# Bus.net
KiCad netlist of a schematic drawn in Altium Designer
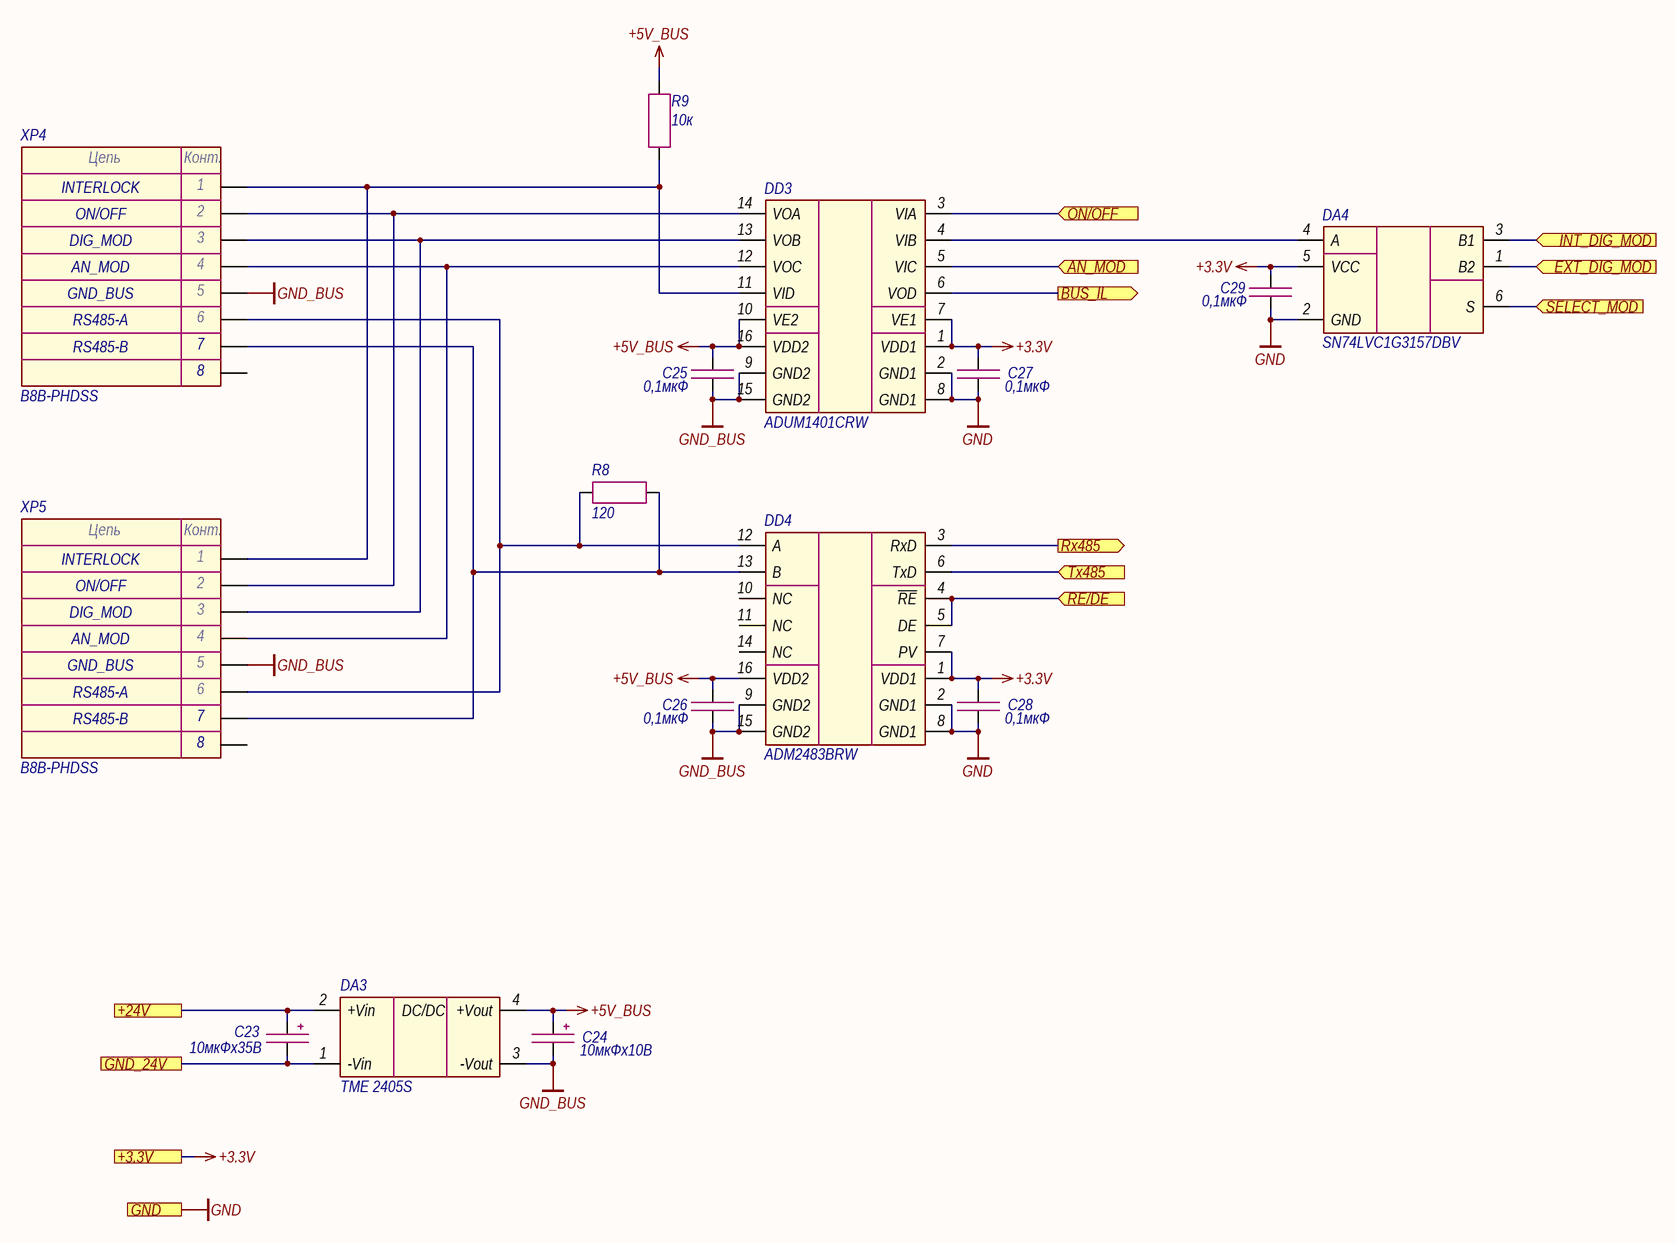
[diagram p0: Bus.SchDoc]

(export (version "E")
  (design (tool "Eeschema 10.0.6"))
  (components
    (comp (ref "C23")
      (value "10мкФх35B")
      (footprint "Pcb_library:CAP_C")
      (libsource (lib "Schem_library") (part "Capacitor_Polar"))
    )
    (comp (ref "C24")
      (value "10мкФх10B")
      (footprint "Pcb_library:CAP_A")
      (libsource (lib "Schem_library") (part "Capacitor_Polar"))
    )
    (comp (ref "C25")
      (value "0,1мкФ")
      (footprint "Pcb_library:CAP_0603")
      (fields (field (name "MANUFACTURER") "Murata"))
      (libsource (lib "Schem_library") (part "Capacitor"))
    )
    (comp (ref "C26")
      (value "0,1мкФ")
      (footprint "Pcb_library:CAP_0603")
      (fields (field (name "MANUFACTURER") "Murata"))
      (libsource (lib "Schem_library") (part "Capacitor"))
    )
    (comp (ref "C27")
      (value "0,1мкФ")
      (footprint "Pcb_library:CAP_0603")
      (fields (field (name "MANUFACTURER") "Murata"))
      (libsource (lib "Schem_library") (part "Capacitor"))
    )
    (comp (ref "C28")
      (value "0,1мкФ")
      (footprint "Pcb_library:CAP_0603")
      (fields (field (name "MANUFACTURER") "Murata"))
      (libsource (lib "Schem_library") (part "Capacitor"))
    )
    (comp (ref "C29")
      (value "0,1мкФ")
      (footprint "Pcb_library:CAP_0603")
      (fields (field (name "MANUFACTURER") "Murata"))
      (libsource (lib "Schem_library") (part "Capacitor"))
    )
    (comp (ref "DA3")
      (value "TME 2405S")
      (footprint "Pcb_library:TME (SIP-4)")
      (fields (field (name "MANUFACTURER") "Traco Power"))
      (libsource (lib "Schem_library") (part "TME"))
    )
    (comp (ref "DA4")
      (value "SN74LVC1G3157DBV")
      (footprint "Pcb_library:SOT-23-6")
      (fields (field (name "MANUFACTURER") "Texas Instruments"))
      (libsource (lib "Schem_library") (part "SN74LVC1G3157"))
    )
    (comp (ref "DD3")
      (value "ADUM1401CRW")
      (footprint "Pcb_library:SOIC-16W")
      (fields (field (name "MANUFACTURER") "Analog Devices"))
      (libsource (lib "Schem_library") (part "ADUM1401"))
    )
    (comp (ref "DD4")
      (value "ADM2483BRW")
      (footprint "Pcb_library:SOIC-16W")
      (fields (field (name "MANUFACTURER") "Analog Devices"))
      (libsource (lib "Schem_library") (part "ADM2483BRW"))
    )
    (comp (ref "R8")
      (value "120")
      (footprint "Pcb_library:RES_0805")
      (fields (field (name "MANUFACTURER") "Yageo"))
      (libsource (lib "Schem_library") (part "Resistor"))
    )
    (comp (ref "R9")
      (value "10к")
      (footprint "Pcb_library:RES_0603")
      (fields (field (name "MANUFACTURER") "Yageo"))
      (libsource (lib "Schem_library") (part "Resistor"))
    )
    (comp (ref "XP4")
      (value "B8B-PHDSS")
      (footprint "Pcb_library:B8B-PHDSS")
      (fields (field (name "MANUFACTURER") "JST"))
      (libsource (lib "Schem_library") (part "Connector-8"))
    )
    (comp (ref "XP5")
      (value "B8B-PHDSS")
      (footprint "Pcb_library:B8B-PHDSS")
      (fields (field (name "MANUFACTURER") "JST"))
      (libsource (lib "Schem_library") (part "Connector-8"))
    )
  )
  (nets
    (net (code "1") (name "+3.3V") (class "Default")
      (node (ref "C27") (pin "1") (pinfunction "1_1") (pintype "passive"))
      (node (ref "C28") (pin "1") (pinfunction "1_1") (pintype "passive"))
      (node (ref "C29") (pin "1") (pinfunction "1_1") (pintype "passive"))
      (node (ref "DA4") (pin "5") (pinfunction "VCC_5") (pintype "passive"))
      (node (ref "DD3") (pin "1") (pinfunction "VDD1_1") (pintype "passive"))
      (node (ref "DD3") (pin "7") (pinfunction "VE1_7") (pintype "passive"))
      (node (ref "DD4") (pin "1") (pinfunction "VDD1_1") (pintype "passive"))
      (node (ref "DD4") (pin "7") (pinfunction "PV_7") (pintype "passive"))
    )
    (net (code "2") (name "+5V_BUS") (class "Default")
      (node (ref "C24") (pin "1") (pinfunction "1_1") (pintype "passive"))
      (node (ref "C25") (pin "1") (pinfunction "1_1") (pintype "passive"))
      (node (ref "C26") (pin "1") (pinfunction "1_1") (pintype "passive"))
      (node (ref "DA3") (pin "4") (pinfunction "+Vout_4") (pintype "passive"))
      (node (ref "DD3") (pin "10") (pinfunction "VE2_10") (pintype "passive"))
      (node (ref "DD3") (pin "16") (pinfunction "VDD2_16") (pintype "passive"))
      (node (ref "DD4") (pin "16") (pinfunction "VDD2_16") (pintype "passive"))
      (node (ref "R9") (pin "1") (pinfunction "1_1") (pintype "passive"))
    )
    (net (code "3") (name "/+24V") (class "Default")
      (node (ref "C23") (pin "1") (pinfunction "1_1") (pintype "passive"))
      (node (ref "DA3") (pin "2") (pinfunction "+Vin_2") (pintype "passive"))
    )
    (net (code "4") (name "/AN_MOD") (class "Default")
      (node (ref "DD3") (pin "5") (pinfunction "VIC_5") (pintype "passive"))
    )
    (net (code "5") (name "/BUS_IL") (class "Default")
      (node (ref "DD3") (pin "6") (pinfunction "VOD_6") (pintype "passive"))
    )
    (net (code "6") (name "/EXT_DIG_MOD") (class "Default")
      (node (ref "DA4") (pin "1") (pinfunction "B2_1") (pintype "passive"))
    )
    (net (code "7") (name "/GND_24V") (class "Default")
      (node (ref "C23") (pin "2") (pinfunction "2_2") (pintype "passive"))
      (node (ref "DA3") (pin "1") (pinfunction "-Vin_1") (pintype "passive"))
    )
    (net (code "8") (name "/INT_DIG_MOD") (class "Default")
      (node (ref "DA4") (pin "3") (pinfunction "B1_3") (pintype "passive"))
    )
    (net (code "9") (name "/ON{slash}OFF") (class "Default")
      (node (ref "DD3") (pin "3") (pinfunction "VIA_3") (pintype "passive"))
    )
    (net (code "10") (name "/RE{slash}DE") (class "Default")
      (node (ref "DD4") (pin "4") (pinfunction "~{RE}_4") (pintype "passive"))
      (node (ref "DD4") (pin "5") (pinfunction "DE_5") (pintype "passive"))
    )
    (net (code "11") (name "/Rx485") (class "Default")
      (node (ref "DD4") (pin "3") (pinfunction "RxD_3") (pintype "passive"))
    )
    (net (code "12") (name "/SELECT_MOD") (class "Default")
      (node (ref "DA4") (pin "6") (pinfunction "S_6") (pintype "passive"))
    )
    (net (code "13") (name "/Tx485") (class "Default")
      (node (ref "DD4") (pin "6") (pinfunction "TxD_6") (pintype "passive"))
    )
    (net (code "14") (name "GND") (class "Default")
      (node (ref "C27") (pin "2") (pinfunction "2_2") (pintype "passive"))
      (node (ref "C28") (pin "2") (pinfunction "2_2") (pintype "passive"))
      (node (ref "C29") (pin "2") (pinfunction "2_2") (pintype "passive"))
      (node (ref "DA4") (pin "2") (pinfunction "GND_2") (pintype "passive"))
      (node (ref "DD3") (pin "2") (pinfunction "GND1_2") (pintype "passive"))
      (node (ref "DD3") (pin "8") (pinfunction "GND1_8") (pintype "passive"))
      (node (ref "DD4") (pin "2") (pinfunction "GND1_2") (pintype "passive"))
      (node (ref "DD4") (pin "8") (pinfunction "GND1_8") (pintype "passive"))
    )
    (net (code "15") (name "GND_BUS") (class "Default")
      (node (ref "C24") (pin "2") (pinfunction "2_2") (pintype "passive"))
      (node (ref "C25") (pin "2") (pinfunction "2_2") (pintype "passive"))
      (node (ref "C26") (pin "2") (pinfunction "2_2") (pintype "passive"))
      (node (ref "DA3") (pin "3") (pinfunction "-Vout_3") (pintype "passive"))
      (node (ref "DD3") (pin "15") (pinfunction "GND2_15") (pintype "passive"))
      (node (ref "DD3") (pin "9") (pinfunction "GND2_9") (pintype "passive"))
      (node (ref "DD4") (pin "15") (pinfunction "GND2_15") (pintype "passive"))
      (node (ref "DD4") (pin "9") (pinfunction "GND2_9") (pintype "passive"))
      (node (ref "XP4") (pin "5") (pintype "passive"))
      (node (ref "XP5") (pin "5") (pintype "passive"))
    )
    (net (code "16") (name "Net-(DA4-A)") (class "Default")
      (node (ref "DA4") (pin "4") (pinfunction "A_4") (pintype "passive"))
      (node (ref "DD3") (pin "4") (pinfunction "VIB_4") (pintype "passive"))
    )
    (net (code "17") (name "Net-(DD3-VID)") (class "Default")
      (node (ref "DD3") (pin "11") (pinfunction "VID_11") (pintype "passive"))
      (node (ref "R9") (pin "2") (pinfunction "2_2") (pintype "passive"))
      (node (ref "XP4") (pin "1") (pintype "passive"))
      (node (ref "XP5") (pin "1") (pintype "passive"))
    )
    (net (code "18") (name "Net-(DD3-VOA)") (class "Default")
      (node (ref "DD3") (pin "14") (pinfunction "VOA_14") (pintype "passive"))
      (node (ref "XP4") (pin "2") (pintype "passive"))
      (node (ref "XP5") (pin "2") (pintype "passive"))
    )
    (net (code "19") (name "Net-(DD3-VOB)") (class "Default")
      (node (ref "DD3") (pin "13") (pinfunction "VOB_13") (pintype "passive"))
      (node (ref "XP4") (pin "3") (pintype "passive"))
      (node (ref "XP5") (pin "3") (pintype "passive"))
    )
    (net (code "20") (name "Net-(DD3-VOC)") (class "Default")
      (node (ref "DD3") (pin "12") (pinfunction "VOC_12") (pintype "passive"))
      (node (ref "XP4") (pin "4") (pintype "passive"))
      (node (ref "XP5") (pin "4") (pintype "passive"))
    )
    (net (code "21") (name "Net-(DD4-A)") (class "Default")
      (node (ref "DD4") (pin "12") (pinfunction "A_12") (pintype "passive"))
      (node (ref "R8") (pin "1") (pinfunction "1_1") (pintype "passive"))
      (node (ref "XP4") (pin "6") (pintype "passive"))
      (node (ref "XP5") (pin "6") (pintype "passive"))
    )
    (net (code "22") (name "Net-(DD4-B)") (class "Default")
      (node (ref "DD4") (pin "13") (pinfunction "B_13") (pintype "passive"))
      (node (ref "R8") (pin "2") (pinfunction "2_2") (pintype "passive"))
      (node (ref "XP4") (pin "7") (pintype "passive"))
      (node (ref "XP5") (pin "7") (pintype "passive"))
    )
    (net (code "23") (name "unconnected-(DD4-NC-Pad10)") (class "Default")
      (node (ref "DD4") (pin "10") (pinfunction "NC_10") (pintype "passive"))
    )
    (net (code "24") (name "unconnected-(DD4-NC-Pad11)") (class "Default")
      (node (ref "DD4") (pin "11") (pinfunction "NC_11") (pintype "passive"))
    )
    (net (code "25") (name "unconnected-(DD4-NC-Pad14)") (class "Default")
      (node (ref "DD4") (pin "14") (pinfunction "NC_14") (pintype "passive"))
    )
    (net (code "26") (name "unconnected-(XP4-Pad8)") (class "Default")
      (node (ref "XP4") (pin "8") (pintype "passive"))
    )
    (net (code "27") (name "unconnected-(XP5-Pad8)") (class "Default")
      (node (ref "XP5") (pin "8") (pintype "passive"))
    )
  )
)
